# Supply_5V_to_3V3-_Ams1117.net
KiCad netlist of a schematic drawn in Altium Designer
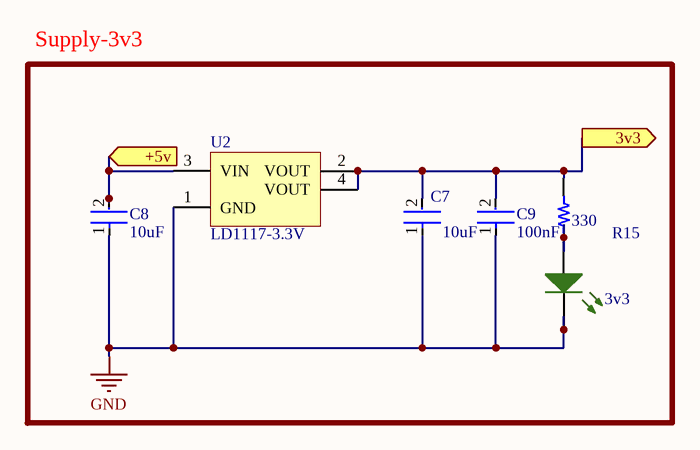
[diagram p0: Supply 5V to 3V3- Ams1117.SchDoc]

(export (version "E")
  (design (tool "Eeschema 10.0.6"))
  (components
    (comp (ref "3v3")
      (value "LED SMD 0805 GREEN")
      (footprint "LED_0805_GREEN")
      (libsource (lib "Led") (part "LED SMD 0805 GREEN"))
    )
    (comp (ref "C7")
      (value "10uF")
      (footprint "FP-C0805C-DN-MFG")
      (description "CAP CER 0.22UF 50V X7R 0805")
      (fields
        (field (name "MANUFACTURER") "KEMET")
        (field (name "OCTOPART") "https://octopart.com/c0805c224k5ractu-kemet-144670")
      )
      (libsource (lib "Altium Content Vault") (part "b4654b650e69147ec39a6b967a45e02"))
    )
    (comp (ref "C8")
      (value "10uF")
      (footprint "FP-C0805C-DN-MFG")
      (description "CAP CER 0.22UF 50V X7R 0805")
      (fields
        (field (name "MANUFACTURER") "KEMET")
        (field (name "OCTOPART") "https://octopart.com/c0805c224k5ractu-kemet-144670")
      )
      (libsource (lib "Altium Content Vault") (part "b4654b650e69147ec39a6b967a45e02"))
    )
    (comp (ref "C9")
      (value "100nF")
      (footprint "FP-C0805C-DN-MFG")
      (description "CAP CER 0.22UF 50V X7R 0805")
      (fields
        (field (name "MANUFACTURER") "KEMET")
        (field (name "OCTOPART") "https://octopart.com/c0805c224k5ractu-kemet-144670")
      )
      (libsource (lib "Altium Content Vault") (part "b4654b650e69147ec39a6b967a45e02"))
    )
    (comp (ref "R15")
      (value "330")
      (footprint "RES 0805_2012")
      (description "SMT Resistor")
      (libsource (lib "Resistor") (part "Res 0805"))
    )
    (comp (ref "U2")
      (value "LD1117-3.3V")
      (footprint "SOT-223-4 6.5X7MM P2.3MM")
      (description "Linear Voltage Regulator IC  1 Output  800mA SOT-223")
      (fields (field (name "PARTNUMBER") "LD1117S33CTR"))
      (libsource (lib "Chip") (part "LD1117-3.3V (SMD SOT-223)"))
    )
  )
  (nets
    (net (code "1") (name "/+5v") (class "Default")
      (node (ref "C8") (pin "2") (pinfunction "2_2") (pintype "passive"))
      (node (ref "U2") (pin "3") (pinfunction "VIN_3") (pintype "passive"))
    )
    (net (code "2") (name "/3v3") (class "Default")
      (node (ref "C7") (pin "2") (pinfunction "2_2") (pintype "passive"))
      (node (ref "C9") (pin "2") (pinfunction "2_2") (pintype "passive"))
      (node (ref "R15") (pin "1") (pinfunction "1_1") (pintype "passive"))
      (node (ref "U2") (pin "2") (pinfunction "VOUT_2") (pintype "passive"))
      (node (ref "U2") (pin "4") (pinfunction "VOUT_4") (pintype "passive"))
    )
    (net (code "3") (name "GND") (class "Default")
      (node (ref "3v3") (pin "2") (pinfunction "K_2") (pintype "passive"))
      (node (ref "C7") (pin "1") (pinfunction "1_1") (pintype "passive"))
      (node (ref "C8") (pin "1") (pinfunction "1_1") (pintype "passive"))
      (node (ref "C9") (pin "1") (pinfunction "1_1") (pintype "passive"))
      (node (ref "U2") (pin "1") (pinfunction "GND_1") (pintype "passive"))
    )
    (net (code "4") (name "Net-(3v3-A)") (class "Default")
      (node (ref "3v3") (pin "1") (pinfunction "A_1") (pintype "passive"))
      (node (ref "R15") (pin "2") (pinfunction "2_2") (pintype "passive"))
    )
  )
)
